# Dc-Dc_Converters.net
KiCad netlist of a schematic drawn in Altium Designer
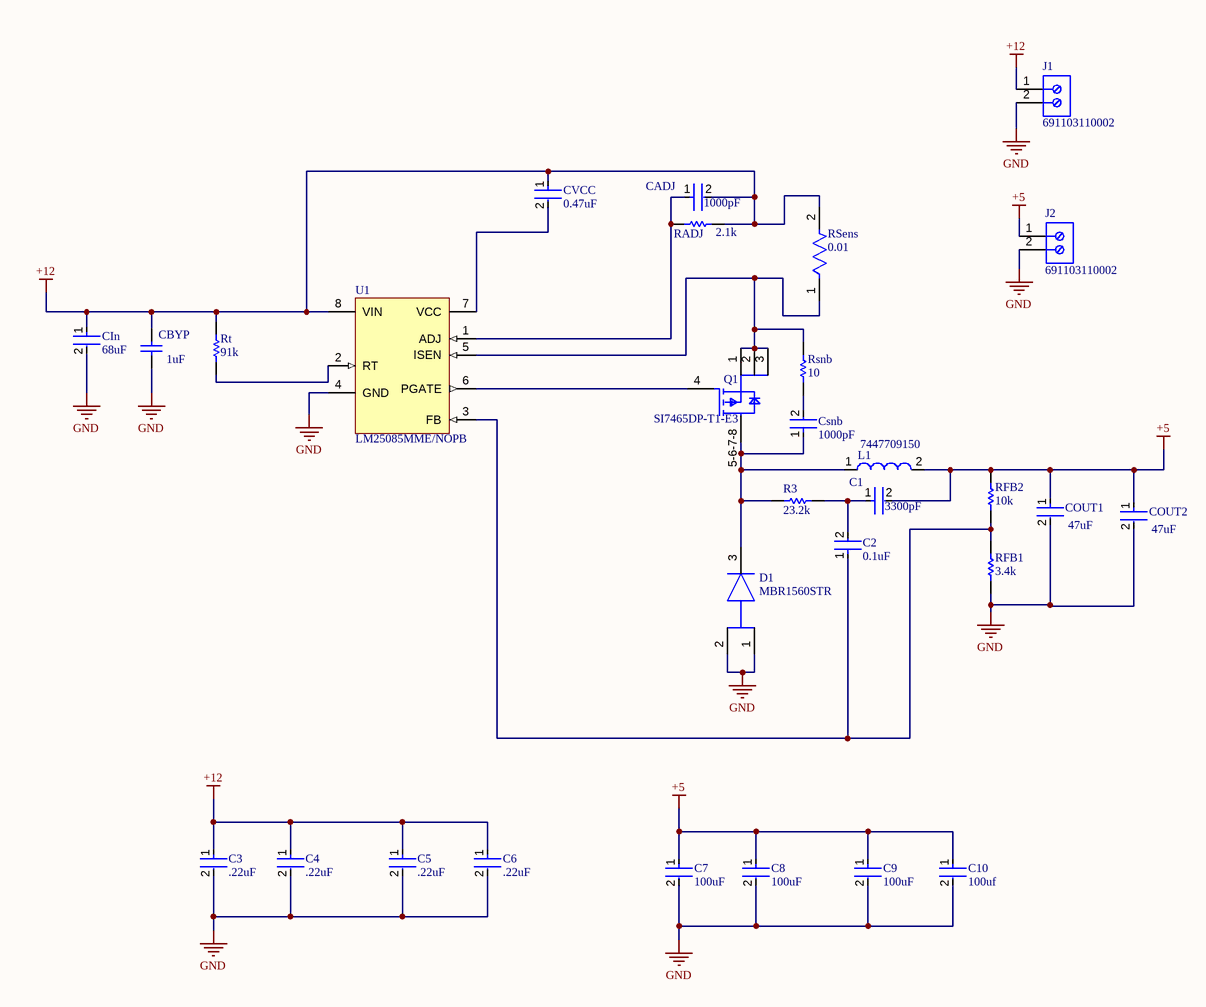
[diagram p0: Dc-Dc Converters.SchDoc]

(export (version "E")
  (design (tool "Eeschema 10.0.6"))
  (components
    (comp (ref "C1")
      (value "3300pF")
      (footprint "FP-C0805C-DG-MFG")
      (description "CAP CER 10UF 10V X5R 0805")
      (fields (field (name "TOLERANCE") "10%") (field (name "MANUFACTURER PART NUMBER") "C0805C106K8PACTU"))
      (libsource (lib "Altium Content Vault") (part "11868f565c42a9108669ba33697ecf6"))
    )
    (comp (ref "C2")
      (value "0.1uF")
      (footprint "FP-C0805C-DG-MFG")
      (description "CAP CER 10UF 10V X5R 0805")
      (fields (field (name "TOLERANCE") "10%") (field (name "MANUFACTURER PART NUMBER") "C0805C106K8PACTU"))
      (libsource (lib "Altium Content Vault") (part "11868f565c42a9108669ba33697ecf6"))
    )
    (comp (ref "C3")
      (value ".22uF")
      (footprint "FP-GRM32-0_3-MFG")
      (description "CAP CER 100UF 6.3V X5R 1210")
      (fields
        (field (name "OCTOPART") "https://octopart.com/grm32er60j107me20l-murata-197007")
        (field (name "3DS PART NUMBER") "220-00002")
      )
      (libsource (lib "Altium Content Vault") (part "11868f565c42a9108669ba33697ecf6"))
    )
    (comp (ref "C4")
      (value ".22uF")
      (footprint "FP-GRM32-0_3-MFG")
      (description "CAP CER 100UF 6.3V X5R 1210")
      (fields
        (field (name "OCTOPART") "https://octopart.com/grm32er60j107me20l-murata-197007")
        (field (name "3DS PART NUMBER") "220-00002")
      )
      (libsource (lib "Altium Content Vault") (part "11868f565c42a9108669ba33697ecf6"))
    )
    (comp (ref "C5")
      (value ".22uF")
      (footprint "FP-GRM32-0_3-MFG")
      (description "CAP CER 100UF 6.3V X5R 1210")
      (fields
        (field (name "OCTOPART") "https://octopart.com/grm32er60j107me20l-murata-197007")
        (field (name "3DS PART NUMBER") "220-00002")
      )
      (libsource (lib "Altium Content Vault") (part "11868f565c42a9108669ba33697ecf6"))
    )
    (comp (ref "C6")
      (value ".22uF")
      (footprint "FP-GRM32-0_3-MFG")
      (description "CAP CER 100UF 6.3V X5R 1210")
      (fields
        (field (name "OCTOPART") "https://octopart.com/grm32er60j107me20l-murata-197007")
        (field (name "3DS PART NUMBER") "220-00002")
      )
      (libsource (lib "Altium Content Vault") (part "11868f565c42a9108669ba33697ecf6"))
    )
    (comp (ref "C7")
      (value "100uF")
      (footprint "FP-GRM32-0_3-MFG")
      (description "CAP CER 100UF 6.3V X5R 1210")
      (fields
        (field (name "OCTOPART") "https://octopart.com/grm32er60j107me20l-murata-197007")
        (field (name "3DS PART NUMBER") "220-00002")
      )
      (libsource (lib "Altium Content Vault") (part "11868f565c42a9108669ba33697ecf6"))
    )
    (comp (ref "C8")
      (value "100uF")
      (footprint "FP-GRM32-0_3-MFG")
      (description "CAP CER 100UF 6.3V X5R 1210")
      (fields
        (field (name "OCTOPART") "https://octopart.com/grm32er60j107me20l-murata-197007")
        (field (name "3DS PART NUMBER") "220-00002")
      )
      (libsource (lib "Altium Content Vault") (part "11868f565c42a9108669ba33697ecf6"))
    )
    (comp (ref "C9")
      (value "100uF")
      (footprint "FP-GRM32-0_3-MFG")
      (description "CAP CER 100UF 6.3V X5R 1210")
      (fields
        (field (name "OCTOPART") "https://octopart.com/grm32er60j107me20l-murata-197007")
        (field (name "3DS PART NUMBER") "220-00002")
      )
      (libsource (lib "Altium Content Vault") (part "11868f565c42a9108669ba33697ecf6"))
    )
    (comp (ref "C10")
      (value "100uf")
      (footprint "FP-GRM32-0_3-MFG")
      (description "CAP CER 100UF 6.3V X5R 1210")
      (fields
        (field (name "OCTOPART") "https://octopart.com/grm32er60j107me20l-murata-197007")
        (field (name "3DS PART NUMBER") "220-00002")
      )
      (libsource (lib "Altium Content Vault") (part "11868f565c42a9108669ba33697ecf6"))
    )
    (comp (ref "CADJ")
      (value "1000pF")
      (footprint "FP-C0805C-DG-MFG")
      (description "CAP CER 10UF 10V X5R 0805")
      (fields (field (name "TOLERANCE") "10%") (field (name "MANUFACTURER PART NUMBER") "C0805C106K8PACTU"))
      (libsource (lib "Altium Content Vault") (part "11868f565c42a9108669ba33697ecf6"))
    )
    (comp (ref "CBYP")
      (value "C1206C105K5RACTU")
      (footprint "CAPC3216X110X50LL20T25")
      (description "Chip Capacitor, 1 uF, +/- 10%, 50 V, -55 to 125 degC, 1206 (3216 Metric), RoHS, Tape and Reel")
      (fields
        (field (name "CAPACITANCE") "1uF")
        (field (name "MANUFACTURER") "Kemet")
        (field (name "TOLERANCE") "10%")
      )
      (libsource (lib "Altium Content Vault") (part "CAP-NP-2"))
    )
    (comp (ref "CIn")
      (value "68uF")
      (footprint "FP-GRM55D-0_4-IPC_A")
      (description "100V 2020 pack")
      (fields (field (name "VOLTAGE") "250V") (field (name "TOLERANCE") "10%"))
      (libsource (lib "Altium Content Vault") (part "b4654b650e69147ec39a6b967a45e02"))
    )
    (comp (ref "COUT1")
      (value "47uF")
      (footprint "FP-GRM32-0_3-MFG")
      (description "CAP CER 100UF 6.3V X5R 1210")
      (fields
        (field (name "OCTOPART") "https://octopart.com/grm32er60j107me20l-murata-197007")
        (field (name "3DS PART NUMBER") "220-00002")
      )
      (libsource (lib "Altium Content Vault") (part "11868f565c42a9108669ba33697ecf6"))
    )
    (comp (ref "COUT2")
      (value "47uF")
      (footprint "FP-GRM32-0_3-MFG")
      (description "CAP CER 100UF 6.3V X5R 1210")
      (fields
        (field (name "OCTOPART") "https://octopart.com/grm32er60j107me20l-murata-197007")
        (field (name "3DS PART NUMBER") "220-00002")
      )
      (libsource (lib "Altium Content Vault") (part "11868f565c42a9108669ba33697ecf6"))
    )
    (comp (ref "Csnb")
      (value "1000pF")
      (footprint "FP-C0805C-DG-MFG")
      (description "CAP CER 10UF 10V X5R 0805")
      (fields (field (name "TOLERANCE") "10%") (field (name "MANUFACTURER PART NUMBER") "C0805C106K8PACTU"))
      (libsource (lib "Altium Content Vault") (part "11868f565c42a9108669ba33697ecf6"))
    )
    (comp (ref "CVCC")
      (value "0.47uF")
      (footprint "FP-C0805C-DG-MFG")
      (description "CAP CER 10UF 10V X5R 0805")
      (fields (field (name "TOLERANCE") "10%") (field (name "MANUFACTURER PART NUMBER") "C0805C106K8PACTU"))
      (libsource (lib "Altium Content Vault") (part "11868f565c42a9108669ba33697ecf6"))
    )
    (comp (ref "D1")
      (value "MBR1560STR")
      (footprint "FP-340BQ-MFG")
      (description "DIODE SCHOTTKY 60V 10A TO277-3")
      (fields
        (field (name "MANUFACTURER") "ON Semiconductor")
        (field (name "OCTOPART") "https://octopart.com/fsv1060v-on+semiconductor-84328651")
      )
      (libsource (lib "Altium Content Vault") (part "4936ed7bdd82a3c6bbc3cb868a43564"))
    )
    (comp (ref "J1")
      (value "691103110002")
      (footprint "691103110002")
      (description "Series 1031 - 3.50 mm Horizontal Entry Modular with Pressure Clamp WR-TBL, 2 pin")
      (fields (field (name "MANUFACTURER") "Wurth Elektronik") (field (name "PUBLISHER") "WurthElektronik"))
      (libsource (lib "Altium Content Vault") (part "WE-CN-1P-F-TB2"))
    )
    (comp (ref "J2")
      (value "691103110002")
      (footprint "691103110002")
      (description "Series 1031 - 3.50 mm Horizontal Entry Modular with Pressure Clamp WR-TBL, 2 pin")
      (fields (field (name "MANUFACTURER") "Wurth Elektronik") (field (name "PUBLISHER") "WurthElektronik"))
      (libsource (lib "Altium Content Vault") (part "WE-CN-1P-F-TB2"))
    )
    (comp (ref "L1")
      (value "7447709150")
      (footprint "WE-PD-XXL")
      (description "SMD-Shielded Power Inductor WE-PD, L = 15.0 µH")
      (libsource (lib "Altium Content Vault") (part "PAS-IND-INDUCTOR-2"))
    )
    (comp (ref "Q1")
      (value "SI7465DP-T1-E3")
      (footprint "FP-S17-0173-SINGLE-MFG")
      (description "MOSFET P-CH 60V 3.2A PPAK SO-8")
      (fields
        (field (name "OCTOPART") "https://octopart.com/si7145dp-t1-ge3-vishay-42623172")
        (field (name "MANUFACTURER") "Vishay")
      )
      (libsource (lib "Altium Content Vault") (part "69475525114238b3975de0d3db13512"))
    )
    (comp (ref "R3")
      (value "23.2k")
      (footprint "RESC2013X50X30LL20T20")
      (fields (field (name "MANUFACTURER") "Vishay Dale") (field (name "PART NUMBER") "CRCW08050000Z0EA"))
      (libsource (lib "Altium Content Vault") (part "RES"))
    )
    (comp (ref "RADJ")
      (value "2.1k")
      (footprint "RESC2013X50X30LL20T20")
      (fields (field (name "MANUFACTURER") "Vishay Dale") (field (name "PART NUMBER") "CRCW08050000Z0EA"))
      (libsource (lib "Altium Content Vault") (part "RES"))
    )
    (comp (ref "RFB1")
      (value "3.4k")
      (footprint "RESC2013X50X30LL20T20")
      (fields (field (name "MANUFACTURER") "Vishay Dale") (field (name "PART NUMBER") "CRCW08050000Z0EA"))
      (libsource (lib "Altium Content Vault") (part "RES"))
    )
    (comp (ref "RFB2")
      (value "10k")
      (footprint "RESC2013X50X30LL20T20")
      (fields (field (name "MANUFACTURER") "Vishay Dale") (field (name "PART NUMBER") "CRCW08050000Z0EA"))
      (libsource (lib "Altium Content Vault") (part "RES"))
    )
    (comp (ref "RSens")
      (value "0.01")
      (footprint "FP-CRCW2010-e3-MFG")
      (description "RES Thick Film, 49.9Ω, 1%, 0.75W, 100ppm/°C, 2010")
      (fields (field (name "TOLERANCE") "1%"))
      (libsource (lib "Altium Content Vault") (part "1029c3af85768c4190bb7ad29bc67b5"))
    )
    (comp (ref "Rsnb")
      (value "10")
      (footprint "RESC2013X50X30LL20T20")
      (fields (field (name "MANUFACTURER") "Vishay Dale") (field (name "PART NUMBER") "CRCW08050000Z0EA"))
      (libsource (lib "Altium Content Vault") (part "RES"))
    )
    (comp (ref "Rt")
      (value "91k")
      (footprint "RESC2013X50X30LL20T20")
      (fields (field (name "MANUFACTURER") "Vishay Dale") (field (name "PART NUMBER") "CRCW08050000Z0EA"))
      (libsource (lib "Altium Content Vault") (part "RES"))
    )
    (comp (ref "U1")
      (value "LM25085MME/NOPB")
      (footprint "DGK0008A_M")
      (description "42V Constant On-Time PFET Buck Switching Controller, 8-pin MSOP, Pb-Free")
      (fields (field (name "MANUFACTURER") "Texas Instruments"))
      (libsource (lib "Altium Content Vault") (part "PM-SWREG-LM25085-IL8"))
    )
  )
  (nets
    (net (code "1") (name "+5") (class "Default")
      (node (ref "C1") (pin "2") (pinfunction "2_2") (pintype "passive"))
      (node (ref "C10") (pin "1") (pinfunction "1_1") (pintype "passive"))
      (node (ref "C7") (pin "1") (pinfunction "1_1") (pintype "passive"))
      (node (ref "C8") (pin "1") (pinfunction "1_1") (pintype "passive"))
      (node (ref "C9") (pin "1") (pinfunction "1_1") (pintype "passive"))
      (node (ref "COUT1") (pin "1") (pinfunction "1_1") (pintype "passive"))
      (node (ref "COUT2") (pin "1") (pinfunction "1_1") (pintype "passive"))
      (node (ref "J2") (pin "1") (pinfunction "1_1") (pintype "passive"))
      (node (ref "L1") (pin "2") (pinfunction "2_2") (pintype "passive"))
      (node (ref "RFB2") (pin "1") (pinfunction "1_1") (pintype "passive"))
    )
    (net (code "2") (name "+12") (class "Default")
      (node (ref "C3") (pin "1") (pinfunction "1_1") (pintype "passive"))
      (node (ref "C4") (pin "1") (pinfunction "1_1") (pintype "passive"))
      (node (ref "C5") (pin "1") (pinfunction "1_1") (pintype "passive"))
      (node (ref "C6") (pin "1") (pinfunction "1_1") (pintype "passive"))
      (node (ref "CADJ") (pin "2") (pinfunction "2_2") (pintype "passive"))
      (node (ref "CBYP") (pin "2") (pinfunction "2_2") (pintype "passive"))
      (node (ref "CIn") (pin "1") (pinfunction "1_1") (pintype "passive"))
      (node (ref "CVCC") (pin "1") (pinfunction "1_1") (pintype "passive"))
      (node (ref "J1") (pin "1") (pinfunction "1_1") (pintype "passive"))
      (node (ref "RADJ") (pin "1") (pinfunction "1_1") (pintype "passive"))
      (node (ref "RSens") (pin "2") (pinfunction "2_2") (pintype "passive"))
      (node (ref "Rt") (pin "2") (pinfunction "2_2") (pintype "passive"))
      (node (ref "U1") (pin "8") (pinfunction "VIN_8") (pintype "power_in"))
    )
    (net (code "3") (name "GND") (class "Default")
      (node (ref "C10") (pin "2") (pinfunction "2_2") (pintype "passive"))
      (node (ref "C3") (pin "2") (pinfunction "2_2") (pintype "passive"))
      (node (ref "C4") (pin "2") (pinfunction "2_2") (pintype "passive"))
      (node (ref "C5") (pin "2") (pinfunction "2_2") (pintype "passive"))
      (node (ref "C6") (pin "2") (pinfunction "2_2") (pintype "passive"))
      (node (ref "C7") (pin "2") (pinfunction "2_2") (pintype "passive"))
      (node (ref "C8") (pin "2") (pinfunction "2_2") (pintype "passive"))
      (node (ref "C9") (pin "2") (pinfunction "2_2") (pintype "passive"))
      (node (ref "CBYP") (pin "1") (pinfunction "1_1") (pintype "passive"))
      (node (ref "CIn") (pin "2") (pinfunction "2_2") (pintype "passive"))
      (node (ref "COUT1") (pin "2") (pinfunction "2_2") (pintype "passive"))
      (node (ref "COUT2") (pin "2") (pinfunction "2_2") (pintype "passive"))
      (node (ref "D1") (pin "1") (pinfunction "Anode_1_1") (pintype "passive"))
      (node (ref "D1") (pin "2") (pinfunction "Anode_2_2") (pintype "passive"))
      (node (ref "J1") (pin "2") (pinfunction "2_2") (pintype "passive"))
      (node (ref "J2") (pin "2") (pinfunction "2_2") (pintype "passive"))
      (node (ref "RFB1") (pin "1") (pinfunction "1_1") (pintype "passive"))
      (node (ref "U1") (pin "4") (pinfunction "GND_4") (pintype "power_in"))
    )
    (net (code "4") (name "Net-(C1-Pad1)") (class "Default")
      (node (ref "C1") (pin "1") (pinfunction "1_1") (pintype "passive"))
      (node (ref "C2") (pin "2") (pinfunction "2_2") (pintype "passive"))
      (node (ref "R3") (pin "1") (pinfunction "1_1") (pintype "passive"))
    )
    (net (code "5") (name "Net-(Csnb-Pad2)") (class "Default")
      (node (ref "Csnb") (pin "2") (pinfunction "2_2") (pintype "passive"))
      (node (ref "Rsnb") (pin "2") (pinfunction "2_2") (pintype "passive"))
    )
    (net (code "6") (name "Net-(D1-C)") (class "Default")
      (node (ref "Csnb") (pin "1") (pinfunction "1_1") (pintype "passive"))
      (node (ref "D1") (pin "3") (pinfunction "C_3") (pintype "passive"))
      (node (ref "L1") (pin "1") (pinfunction "1_1") (pintype "passive"))
      (node (ref "Q1") (pin "5-6-7-8") (pinfunction "D_5-6-7-8") (pintype "passive"))
      (node (ref "R3") (pin "2") (pinfunction "2_2") (pintype "passive"))
    )
    (net (code "7") (name "Net-(Q1-G)") (class "Default")
      (node (ref "Q1") (pin "4") (pinfunction "G_4") (pintype "passive"))
      (node (ref "U1") (pin "6") (pinfunction "PGATE_6") (pintype "output"))
    )
    (net (code "8") (name "Net-(U1-ADJ)") (class "Default")
      (node (ref "CADJ") (pin "1") (pinfunction "1_1") (pintype "passive"))
      (node (ref "RADJ") (pin "2") (pinfunction "2_2") (pintype "passive"))
      (node (ref "U1") (pin "1") (pinfunction "ADJ_1") (pintype "input"))
    )
    (net (code "9") (name "Net-(U1-FB)") (class "Default")
      (node (ref "C2") (pin "1") (pinfunction "1_1") (pintype "passive"))
      (node (ref "RFB1") (pin "2") (pinfunction "2_2") (pintype "passive"))
      (node (ref "RFB2") (pin "2") (pinfunction "2_2") (pintype "passive"))
      (node (ref "U1") (pin "3") (pinfunction "FB_3") (pintype "input"))
    )
    (net (code "10") (name "Net-(U1-ISEN)") (class "Default")
      (node (ref "Q1") (pin "1") (pinfunction "S_1") (pintype "passive"))
      (node (ref "Q1") (pin "2") (pinfunction "S_2") (pintype "passive"))
      (node (ref "Q1") (pin "3") (pinfunction "S_3") (pintype "passive"))
      (node (ref "RSens") (pin "1") (pinfunction "1_1") (pintype "passive"))
      (node (ref "Rsnb") (pin "1") (pinfunction "1_1") (pintype "passive"))
      (node (ref "U1") (pin "5") (pinfunction "ISEN_5") (pintype "input"))
    )
    (net (code "11") (name "Net-(U1-RT)") (class "Default")
      (node (ref "Rt") (pin "1") (pinfunction "1_1") (pintype "passive"))
      (node (ref "U1") (pin "2") (pinfunction "RT_2") (pintype "input"))
    )
    (net (code "12") (name "Net-(U1-VCC)") (class "Default")
      (node (ref "CVCC") (pin "2") (pinfunction "2_2") (pintype "passive"))
      (node (ref "U1") (pin "7") (pinfunction "VCC_7") (pintype "power_in"))
    )
  )
)
